# FPGA_7A35T_POWER.net
KiCad netlist of a schematic drawn in Altium Designer
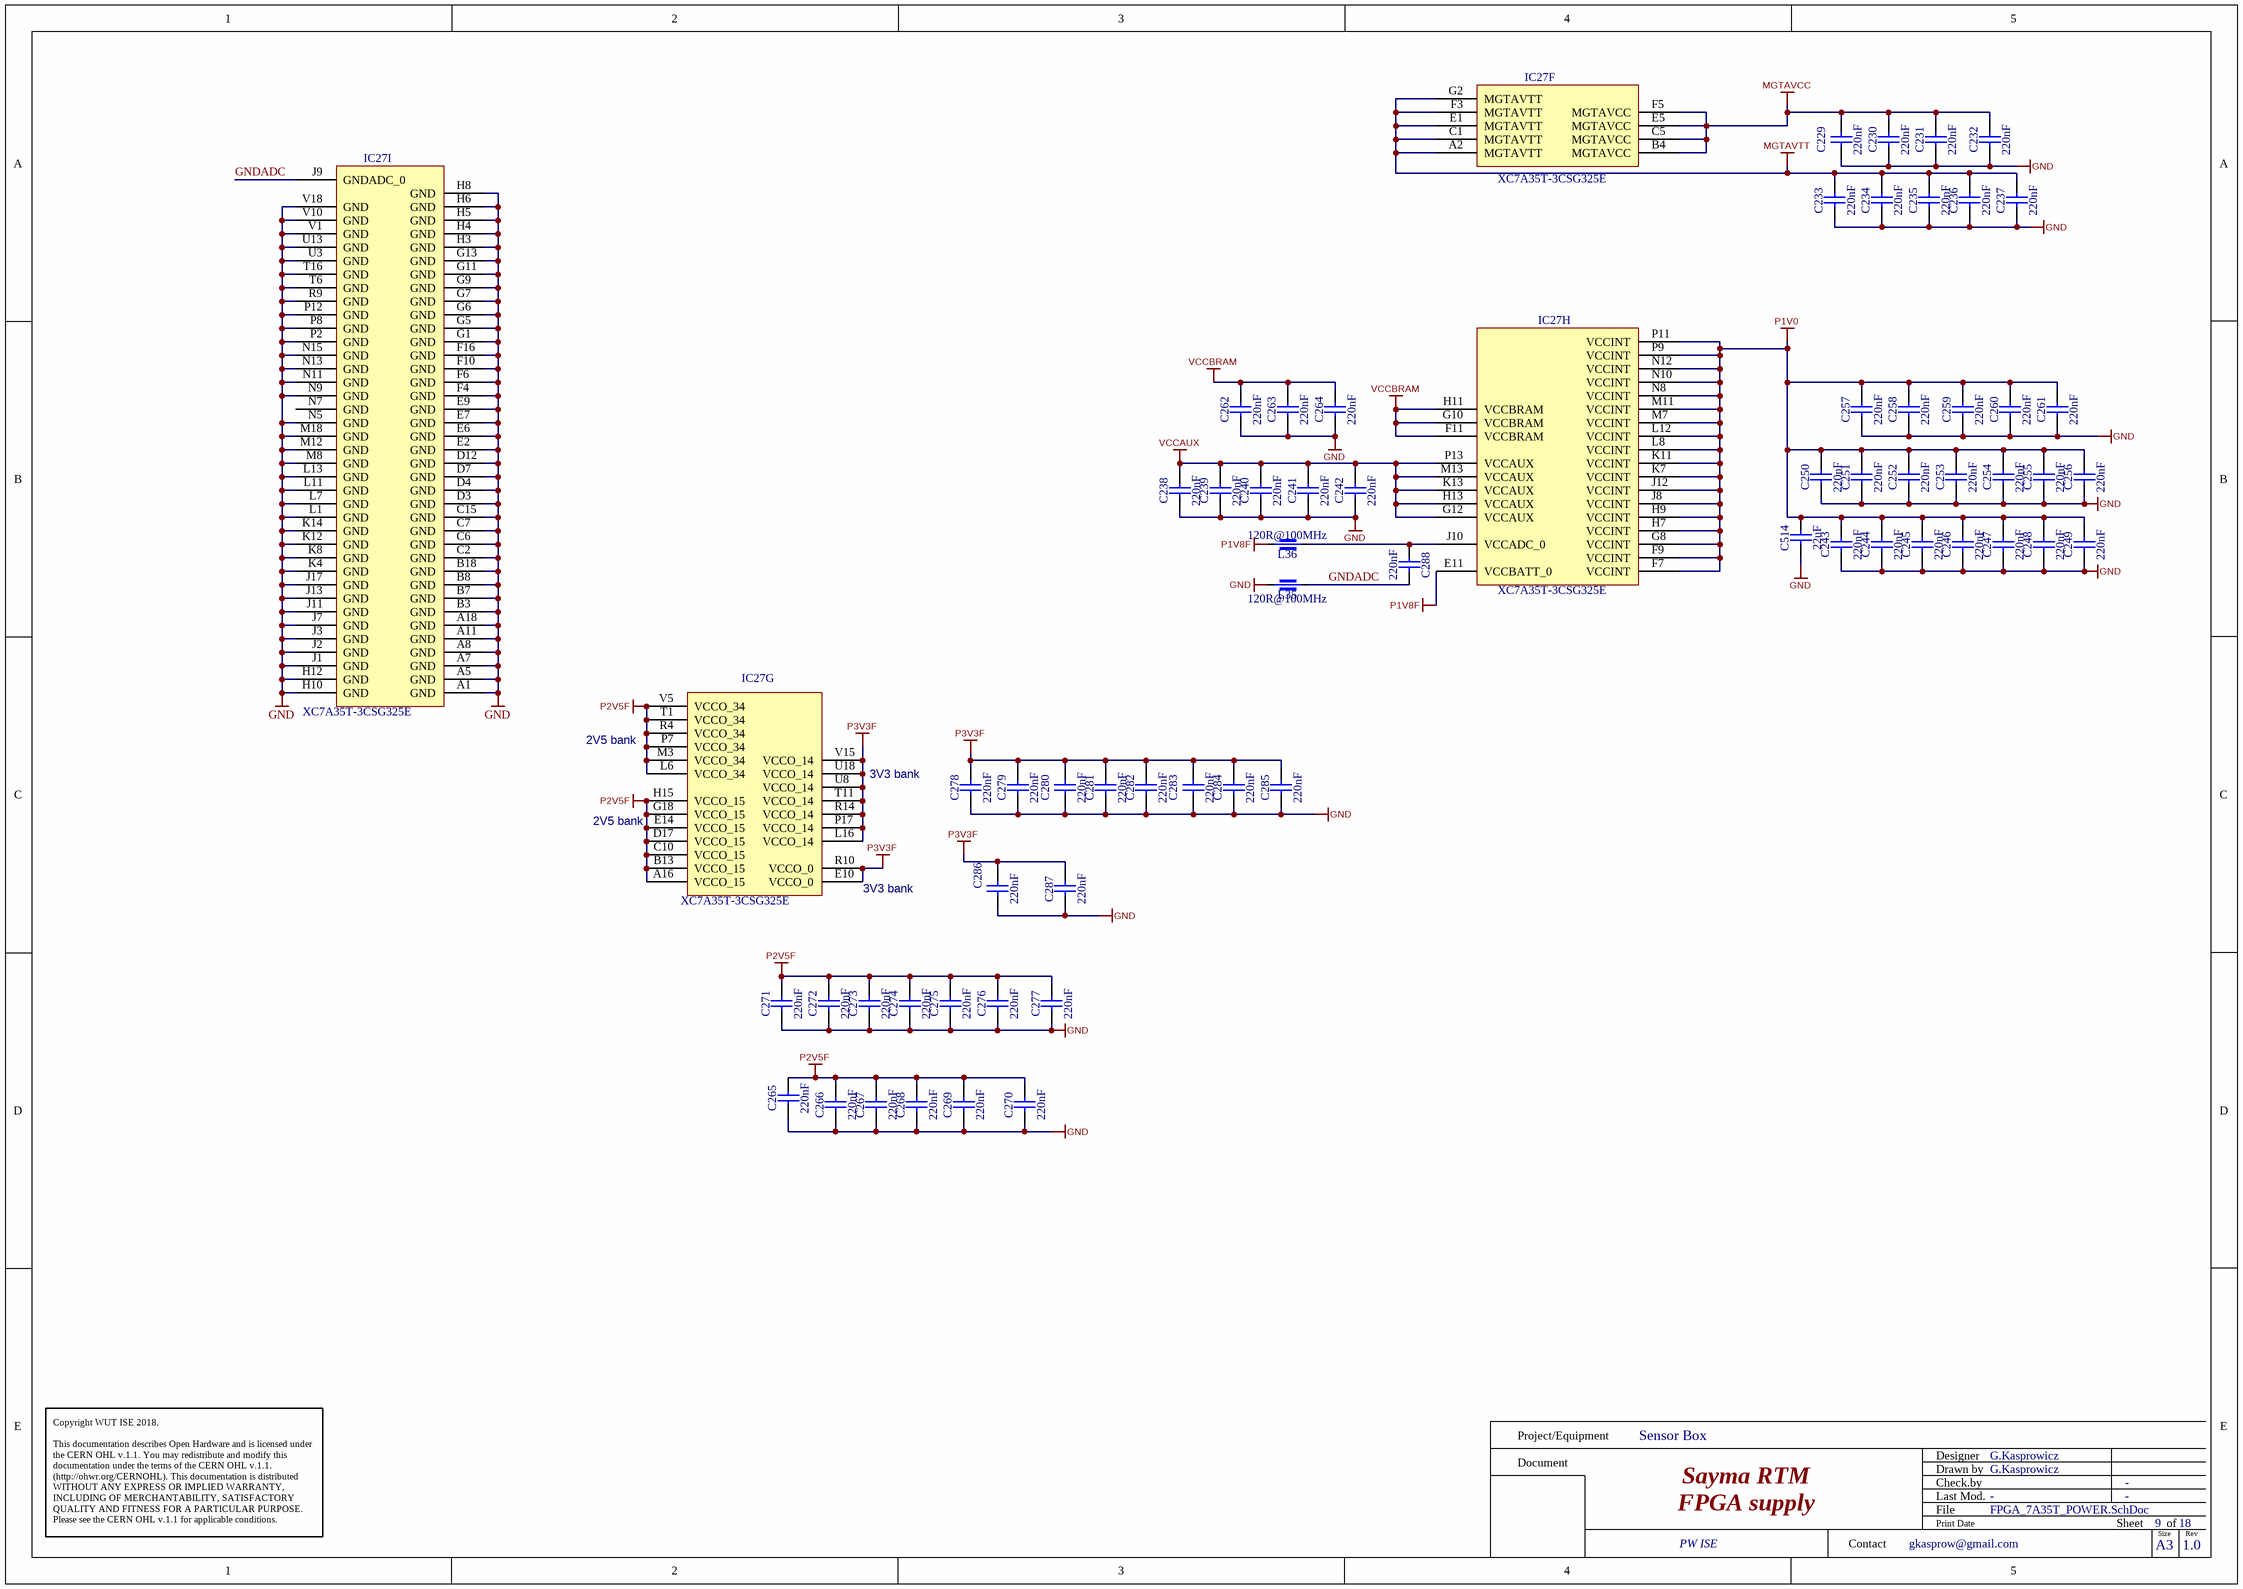
[diagram p0: FPGA_7A35T_POWER.SchDoc]

(export (version "E")
  (design (tool "Eeschema 10.0.6"))
  (components
    (comp (ref "C229")
      (value "220nF")
      (footprint "CAPC0603X33N")
      (description "Non-polarised capacitor")
      (fields
        (field (name "MANUFACTURER PART NUMBER") "CC0201_220NF_6.3V_20%_X5R")
        (field (name "MANUFACTURER") "GENERIC")
        (field (name "AUTHOR") "CERN DEM JLC")
      )
      (libsource (lib "Capacitors") (part "Capacitor - non polarized"))
    )
    (comp (ref "C230")
      (value "220nF")
      (footprint "CAPC0603X33N")
      (description "Non-polarised capacitor")
      (fields
        (field (name "MANUFACTURER PART NUMBER") "CC0201_220NF_6.3V_20%_X5R")
        (field (name "MANUFACTURER") "GENERIC")
        (field (name "AUTHOR") "CERN DEM JLC")
      )
      (libsource (lib "Capacitors") (part "Capacitor - non polarized"))
    )
    (comp (ref "C231")
      (value "220nF")
      (footprint "CAPC0603X33N")
      (description "Non-polarised capacitor")
      (fields
        (field (name "MANUFACTURER PART NUMBER") "CC0201_220NF_6.3V_20%_X5R")
        (field (name "MANUFACTURER") "GENERIC")
        (field (name "AUTHOR") "CERN DEM JLC")
      )
      (libsource (lib "Capacitors") (part "Capacitor - non polarized"))
    )
    (comp (ref "C232")
      (value "220nF")
      (footprint "CAPC0603X33N")
      (description "Non-polarised capacitor")
      (fields
        (field (name "MANUFACTURER PART NUMBER") "CC0201_220NF_6.3V_20%_X5R")
        (field (name "MANUFACTURER") "GENERIC")
        (field (name "AUTHOR") "CERN DEM JLC")
      )
      (libsource (lib "Capacitors") (part "Capacitor - non polarized"))
    )
    (comp (ref "C233")
      (value "220nF")
      (footprint "CAPC0603X33N")
      (description "Non-polarised capacitor")
      (fields
        (field (name "MANUFACTURER PART NUMBER") "CC0201_220NF_6.3V_20%_X5R")
        (field (name "MANUFACTURER") "GENERIC")
        (field (name "AUTHOR") "CERN DEM JLC")
      )
      (libsource (lib "Capacitors") (part "Capacitor - non polarized"))
    )
    (comp (ref "C234")
      (value "220nF")
      (footprint "CAPC0603X33N")
      (description "Non-polarised capacitor")
      (fields
        (field (name "MANUFACTURER PART NUMBER") "CC0201_220NF_6.3V_20%_X5R")
        (field (name "MANUFACTURER") "GENERIC")
        (field (name "AUTHOR") "CERN DEM JLC")
      )
      (libsource (lib "Capacitors") (part "Capacitor - non polarized"))
    )
    (comp (ref "C235")
      (value "220nF")
      (footprint "CAPC0603X33N")
      (description "Non-polarised capacitor")
      (fields
        (field (name "MANUFACTURER PART NUMBER") "CC0201_220NF_6.3V_20%_X5R")
        (field (name "MANUFACTURER") "GENERIC")
        (field (name "AUTHOR") "CERN DEM JLC")
      )
      (libsource (lib "Capacitors") (part "Capacitor - non polarized"))
    )
    (comp (ref "C236")
      (value "220nF")
      (footprint "CAPC0603X33N")
      (description "Non-polarised capacitor")
      (fields
        (field (name "MANUFACTURER PART NUMBER") "CC0201_220NF_6.3V_20%_X5R")
        (field (name "MANUFACTURER") "GENERIC")
        (field (name "AUTHOR") "CERN DEM JLC")
      )
      (libsource (lib "Capacitors") (part "Capacitor - non polarized"))
    )
    (comp (ref "C237")
      (value "220nF")
      (footprint "CAPC0603X33N")
      (description "Non-polarised capacitor")
      (fields
        (field (name "MANUFACTURER PART NUMBER") "CC0201_220NF_6.3V_20%_X5R")
        (field (name "MANUFACTURER") "GENERIC")
        (field (name "AUTHOR") "CERN DEM JLC")
      )
      (libsource (lib "Capacitors") (part "Capacitor - non polarized"))
    )
    (comp (ref "C238")
      (value "220nF")
      (footprint "CAPC0603X33N")
      (description "Non-polarised capacitor")
      (fields
        (field (name "MANUFACTURER PART NUMBER") "CC0201_220NF_6.3V_20%_X5R")
        (field (name "MANUFACTURER") "GENERIC")
        (field (name "AUTHOR") "CERN DEM JLC")
      )
      (libsource (lib "Capacitors") (part "Capacitor - non polarized"))
    )
    (comp (ref "C239")
      (value "220nF")
      (footprint "CAPC0603X33N")
      (description "Non-polarised capacitor")
      (fields
        (field (name "MANUFACTURER PART NUMBER") "CC0201_220NF_6.3V_20%_X5R")
        (field (name "MANUFACTURER") "GENERIC")
        (field (name "AUTHOR") "CERN DEM JLC")
      )
      (libsource (lib "Capacitors") (part "Capacitor - non polarized"))
    )
    (comp (ref "C240")
      (value "220nF")
      (footprint "CAPC0603X33N")
      (description "Non-polarised capacitor")
      (fields
        (field (name "MANUFACTURER PART NUMBER") "CC0201_220NF_6.3V_20%_X5R")
        (field (name "MANUFACTURER") "GENERIC")
        (field (name "AUTHOR") "CERN DEM JLC")
      )
      (libsource (lib "Capacitors") (part "Capacitor - non polarized"))
    )
    (comp (ref "C241")
      (value "220nF")
      (footprint "CAPC0603X33N")
      (description "Non-polarised capacitor")
      (fields
        (field (name "MANUFACTURER PART NUMBER") "CC0201_220NF_6.3V_20%_X5R")
        (field (name "MANUFACTURER") "GENERIC")
        (field (name "AUTHOR") "CERN DEM JLC")
      )
      (libsource (lib "Capacitors") (part "Capacitor - non polarized"))
    )
    (comp (ref "C242")
      (value "220nF")
      (footprint "CAPC0603X33N")
      (description "Non-polarised capacitor")
      (fields
        (field (name "MANUFACTURER PART NUMBER") "CC0201_220NF_6.3V_20%_X5R")
        (field (name "MANUFACTURER") "GENERIC")
        (field (name "AUTHOR") "CERN DEM JLC")
      )
      (libsource (lib "Capacitors") (part "Capacitor - non polarized"))
    )
    (comp (ref "C243")
      (value "220nF")
      (footprint "CAPC0603X33N")
      (description "Non-polarised capacitor")
      (fields
        (field (name "MANUFACTURER PART NUMBER") "CC0201_220NF_6.3V_20%_X5R")
        (field (name "MANUFACTURER") "GENERIC")
        (field (name "AUTHOR") "CERN DEM JLC")
      )
      (libsource (lib "Capacitors") (part "Capacitor - non polarized"))
    )
    (comp (ref "C244")
      (value "220nF")
      (footprint "CAPC0603X33N")
      (description "Non-polarised capacitor")
      (fields
        (field (name "MANUFACTURER PART NUMBER") "CC0201_220NF_6.3V_20%_X5R")
        (field (name "MANUFACTURER") "GENERIC")
        (field (name "AUTHOR") "CERN DEM JLC")
      )
      (libsource (lib "Capacitors") (part "Capacitor - non polarized"))
    )
    (comp (ref "C245")
      (value "220nF")
      (footprint "CAPC0603X33N")
      (description "Non-polarised capacitor")
      (fields
        (field (name "MANUFACTURER PART NUMBER") "CC0201_220NF_6.3V_20%_X5R")
        (field (name "MANUFACTURER") "GENERIC")
        (field (name "AUTHOR") "CERN DEM JLC")
      )
      (libsource (lib "Capacitors") (part "Capacitor - non polarized"))
    )
    (comp (ref "C246")
      (value "220nF")
      (footprint "CAPC0603X33N")
      (description "Non-polarised capacitor")
      (fields
        (field (name "MANUFACTURER PART NUMBER") "CC0201_220NF_6.3V_20%_X5R")
        (field (name "MANUFACTURER") "GENERIC")
        (field (name "AUTHOR") "CERN DEM JLC")
      )
      (libsource (lib "Capacitors") (part "Capacitor - non polarized"))
    )
    (comp (ref "C247")
      (value "220nF")
      (footprint "CAPC0603X33N")
      (description "Non-polarised capacitor")
      (fields
        (field (name "MANUFACTURER PART NUMBER") "CC0201_220NF_6.3V_20%_X5R")
        (field (name "MANUFACTURER") "GENERIC")
        (field (name "AUTHOR") "CERN DEM JLC")
      )
      (libsource (lib "Capacitors") (part "Capacitor - non polarized"))
    )
    (comp (ref "C248")
      (value "220nF")
      (footprint "CAPC0603X33N")
      (description "Non-polarised capacitor")
      (fields
        (field (name "MANUFACTURER PART NUMBER") "CC0201_220NF_6.3V_20%_X5R")
        (field (name "MANUFACTURER") "GENERIC")
        (field (name "AUTHOR") "CERN DEM JLC")
      )
      (libsource (lib "Capacitors") (part "Capacitor - non polarized"))
    )
    (comp (ref "C249")
      (value "220nF")
      (footprint "CAPC0603X33N")
      (description "Non-polarised capacitor")
      (fields
        (field (name "MANUFACTURER PART NUMBER") "CC0201_220NF_6.3V_20%_X5R")
        (field (name "MANUFACTURER") "GENERIC")
        (field (name "AUTHOR") "CERN DEM JLC")
      )
      (libsource (lib "Capacitors") (part "Capacitor - non polarized"))
    )
    (comp (ref "C250")
      (value "220nF")
      (footprint "CAPC0603X33N")
      (description "Non-polarised capacitor")
      (fields
        (field (name "MANUFACTURER PART NUMBER") "CC0201_220NF_6.3V_20%_X5R")
        (field (name "MANUFACTURER") "GENERIC")
        (field (name "AUTHOR") "CERN DEM JLC")
      )
      (libsource (lib "Capacitors") (part "Capacitor - non polarized"))
    )
    (comp (ref "C251")
      (value "220nF")
      (footprint "CAPC0603X33N")
      (description "Non-polarised capacitor")
      (fields
        (field (name "MANUFACTURER PART NUMBER") "CC0201_220NF_6.3V_20%_X5R")
        (field (name "MANUFACTURER") "GENERIC")
        (field (name "AUTHOR") "CERN DEM JLC")
      )
      (libsource (lib "Capacitors") (part "Capacitor - non polarized"))
    )
    (comp (ref "C252")
      (value "220nF")
      (footprint "CAPC0603X33N")
      (description "Non-polarised capacitor")
      (fields
        (field (name "MANUFACTURER PART NUMBER") "CC0201_220NF_6.3V_20%_X5R")
        (field (name "MANUFACTURER") "GENERIC")
        (field (name "AUTHOR") "CERN DEM JLC")
      )
      (libsource (lib "Capacitors") (part "Capacitor - non polarized"))
    )
    (comp (ref "C253")
      (value "220nF")
      (footprint "CAPC0603X33N")
      (description "Non-polarised capacitor")
      (fields
        (field (name "MANUFACTURER PART NUMBER") "CC0201_220NF_6.3V_20%_X5R")
        (field (name "MANUFACTURER") "GENERIC")
        (field (name "AUTHOR") "CERN DEM JLC")
      )
      (libsource (lib "Capacitors") (part "Capacitor - non polarized"))
    )
    (comp (ref "C254")
      (value "220nF")
      (footprint "CAPC0603X33N")
      (description "Non-polarised capacitor")
      (fields
        (field (name "MANUFACTURER PART NUMBER") "CC0201_220NF_6.3V_20%_X5R")
        (field (name "MANUFACTURER") "GENERIC")
        (field (name "AUTHOR") "CERN DEM JLC")
      )
      (libsource (lib "Capacitors") (part "Capacitor - non polarized"))
    )
    (comp (ref "C255")
      (value "220nF")
      (footprint "CAPC0603X33N")
      (description "Non-polarised capacitor")
      (fields
        (field (name "MANUFACTURER PART NUMBER") "CC0201_220NF_6.3V_20%_X5R")
        (field (name "MANUFACTURER") "GENERIC")
        (field (name "AUTHOR") "CERN DEM JLC")
      )
      (libsource (lib "Capacitors") (part "Capacitor - non polarized"))
    )
    (comp (ref "C256")
      (value "220nF")
      (footprint "CAPC0603X33N")
      (description "Non-polarised capacitor")
      (fields
        (field (name "MANUFACTURER PART NUMBER") "CC0201_220NF_6.3V_20%_X5R")
        (field (name "MANUFACTURER") "GENERIC")
        (field (name "AUTHOR") "CERN DEM JLC")
      )
      (libsource (lib "Capacitors") (part "Capacitor - non polarized"))
    )
    (comp (ref "C257")
      (value "220nF")
      (footprint "CAPC0603X33N")
      (description "Non-polarised capacitor")
      (fields
        (field (name "MANUFACTURER PART NUMBER") "CC0201_220NF_6.3V_20%_X5R")
        (field (name "MANUFACTURER") "GENERIC")
        (field (name "AUTHOR") "CERN DEM JLC")
      )
      (libsource (lib "Capacitors") (part "Capacitor - non polarized"))
    )
    (comp (ref "C258")
      (value "220nF")
      (footprint "CAPC0603X33N")
      (description "Non-polarised capacitor")
      (fields
        (field (name "MANUFACTURER PART NUMBER") "CC0201_220NF_6.3V_20%_X5R")
        (field (name "MANUFACTURER") "GENERIC")
        (field (name "AUTHOR") "CERN DEM JLC")
      )
      (libsource (lib "Capacitors") (part "Capacitor - non polarized"))
    )
    (comp (ref "C259")
      (value "220nF")
      (footprint "CAPC0603X33N")
      (description "Non-polarised capacitor")
      (fields
        (field (name "MANUFACTURER PART NUMBER") "CC0201_220NF_6.3V_20%_X5R")
        (field (name "MANUFACTURER") "GENERIC")
        (field (name "AUTHOR") "CERN DEM JLC")
      )
      (libsource (lib "Capacitors") (part "Capacitor - non polarized"))
    )
    (comp (ref "C260")
      (value "220nF")
      (footprint "CAPC0603X33N")
      (description "Non-polarised capacitor")
      (fields
        (field (name "MANUFACTURER PART NUMBER") "CC0201_220NF_6.3V_20%_X5R")
        (field (name "MANUFACTURER") "GENERIC")
        (field (name "AUTHOR") "CERN DEM JLC")
      )
      (libsource (lib "Capacitors") (part "Capacitor - non polarized"))
    )
    (comp (ref "C261")
      (value "220nF")
      (footprint "CAPC0603X33N")
      (description "Non-polarised capacitor")
      (fields
        (field (name "MANUFACTURER PART NUMBER") "CC0201_220NF_6.3V_20%_X5R")
        (field (name "MANUFACTURER") "GENERIC")
        (field (name "AUTHOR") "CERN DEM JLC")
      )
      (libsource (lib "Capacitors") (part "Capacitor - non polarized"))
    )
    (comp (ref "C262")
      (value "220nF")
      (footprint "CAPC0603X33N")
      (description "Non-polarised capacitor")
      (fields
        (field (name "MANUFACTURER PART NUMBER") "CC0201_220NF_6.3V_20%_X5R")
        (field (name "MANUFACTURER") "GENERIC")
        (field (name "AUTHOR") "CERN DEM JLC")
      )
      (libsource (lib "Capacitors") (part "Capacitor - non polarized"))
    )
    (comp (ref "C263")
      (value "220nF")
      (footprint "CAPC0603X33N")
      (description "Non-polarised capacitor")
      (fields
        (field (name "MANUFACTURER PART NUMBER") "CC0201_220NF_6.3V_20%_X5R")
        (field (name "MANUFACTURER") "GENERIC")
        (field (name "AUTHOR") "CERN DEM JLC")
      )
      (libsource (lib "Capacitors") (part "Capacitor - non polarized"))
    )
    (comp (ref "C264")
      (value "220nF")
      (footprint "CAPC0603X33N")
      (description "Non-polarised capacitor")
      (fields
        (field (name "MANUFACTURER PART NUMBER") "CC0201_220NF_6.3V_20%_X5R")
        (field (name "MANUFACTURER") "GENERIC")
        (field (name "AUTHOR") "CERN DEM JLC")
      )
      (libsource (lib "Capacitors") (part "Capacitor - non polarized"))
    )
    (comp (ref "C265")
      (value "220nF")
      (footprint "CAPC0603X33N")
      (description "Non-polarised capacitor")
      (fields
        (field (name "MANUFACTURER PART NUMBER") "CC0201_220NF_6.3V_20%_X5R")
        (field (name "MANUFACTURER") "GENERIC")
        (field (name "AUTHOR") "CERN DEM JLC")
      )
      (libsource (lib "Capacitors") (part "Capacitor - non polarized"))
    )
    (comp (ref "C266")
      (value "220nF")
      (footprint "CAPC0603X33N")
      (description "Non-polarised capacitor")
      (fields
        (field (name "MANUFACTURER PART NUMBER") "CC0201_220NF_6.3V_20%_X5R")
        (field (name "MANUFACTURER") "GENERIC")
        (field (name "AUTHOR") "CERN DEM JLC")
      )
      (libsource (lib "Capacitors") (part "Capacitor - non polarized"))
    )
    (comp (ref "C267")
      (value "220nF")
      (footprint "CAPC0603X33N")
      (description "Non-polarised capacitor")
      (fields
        (field (name "MANUFACTURER PART NUMBER") "CC0201_220NF_6.3V_20%_X5R")
        (field (name "MANUFACTURER") "GENERIC")
        (field (name "AUTHOR") "CERN DEM JLC")
      )
      (libsource (lib "Capacitors") (part "Capacitor - non polarized"))
    )
    (comp (ref "C268")
      (value "220nF")
      (footprint "CAPC0603X33N")
      (description "Non-polarised capacitor")
      (fields
        (field (name "MANUFACTURER PART NUMBER") "CC0201_220NF_6.3V_20%_X5R")
        (field (name "MANUFACTURER") "GENERIC")
        (field (name "AUTHOR") "CERN DEM JLC")
      )
      (libsource (lib "Capacitors") (part "Capacitor - non polarized"))
    )
    (comp (ref "C269")
      (value "220nF")
      (footprint "CAPC0603X33N")
      (description "Non-polarised capacitor")
      (fields
        (field (name "MANUFACTURER PART NUMBER") "CC0201_220NF_6.3V_20%_X5R")
        (field (name "MANUFACTURER") "GENERIC")
        (field (name "AUTHOR") "CERN DEM JLC")
      )
      (libsource (lib "Capacitors") (part "Capacitor - non polarized"))
    )
    (comp (ref "C270")
      (value "220nF")
      (footprint "CAPC0603X33N")
      (description "Non-polarised capacitor")
      (fields
        (field (name "MANUFACTURER PART NUMBER") "CC0201_220NF_6.3V_20%_X5R")
        (field (name "MANUFACTURER") "GENERIC")
        (field (name "AUTHOR") "CERN DEM JLC")
      )
      (libsource (lib "Capacitors") (part "Capacitor - non polarized"))
    )
    (comp (ref "C271")
      (value "220nF")
      (footprint "CAPC0603X33N")
      (description "Non-polarised capacitor")
      (fields
        (field (name "MANUFACTURER PART NUMBER") "CC0201_220NF_6.3V_20%_X5R")
        (field (name "MANUFACTURER") "GENERIC")
        (field (name "AUTHOR") "CERN DEM JLC")
      )
      (libsource (lib "Capacitors") (part "Capacitor - non polarized"))
    )
    (comp (ref "C272")
      (value "220nF")
      (footprint "CAPC0603X33N")
      (description "Non-polarised capacitor")
      (fields
        (field (name "MANUFACTURER PART NUMBER") "CC0201_220NF_6.3V_20%_X5R")
        (field (name "MANUFACTURER") "GENERIC")
        (field (name "AUTHOR") "CERN DEM JLC")
      )
      (libsource (lib "Capacitors") (part "Capacitor - non polarized"))
    )
    (comp (ref "C273")
      (value "220nF")
      (footprint "CAPC0603X33N")
      (description "Non-polarised capacitor")
      (fields
        (field (name "MANUFACTURER PART NUMBER") "CC0201_220NF_6.3V_20%_X5R")
        (field (name "MANUFACTURER") "GENERIC")
        (field (name "AUTHOR") "CERN DEM JLC")
      )
      (libsource (lib "Capacitors") (part "Capacitor - non polarized"))
    )
    (comp (ref "C274")
      (value "220nF")
      (footprint "CAPC0603X33N")
      (description "Non-polarised capacitor")
      (fields
        (field (name "MANUFACTURER PART NUMBER") "CC0201_220NF_6.3V_20%_X5R")
        (field (name "MANUFACTURER") "GENERIC")
        (field (name "AUTHOR") "CERN DEM JLC")
      )
      (libsource (lib "Capacitors") (part "Capacitor - non polarized"))
    )
    (comp (ref "C275")
      (value "220nF")
      (footprint "CAPC0603X33N")
      (description "Non-polarised capacitor")
      (fields
        (field (name "MANUFACTURER PART NUMBER") "CC0201_220NF_6.3V_20%_X5R")
        (field (name "MANUFACTURER") "GENERIC")
        (field (name "AUTHOR") "CERN DEM JLC")
      )
      (libsource (lib "Capacitors") (part "Capacitor - non polarized"))
    )
    (comp (ref "C276")
      (value "220nF")
      (footprint "CAPC0603X33N")
      (description "Non-polarised capacitor")
      (fields
        (field (name "MANUFACTURER PART NUMBER") "CC0201_220NF_6.3V_20%_X5R")
        (field (name "MANUFACTURER") "GENERIC")
        (field (name "AUTHOR") "CERN DEM JLC")
      )
      (libsource (lib "Capacitors") (part "Capacitor - non polarized"))
    )
    (comp (ref "C277")
      (value "220nF")
      (footprint "CAPC0603X33N")
      (description "Non-polarised capacitor")
      (fields
        (field (name "MANUFACTURER PART NUMBER") "CC0201_220NF_6.3V_20%_X5R")
        (field (name "MANUFACTURER") "GENERIC")
        (field (name "AUTHOR") "CERN DEM JLC")
      )
      (libsource (lib "Capacitors") (part "Capacitor - non polarized"))
    )
    (comp (ref "C278")
      (value "220nF")
      (footprint "CAPC0603X33N")
      (description "Non-polarised capacitor")
      (fields
        (field (name "MANUFACTURER PART NUMBER") "CC0201_220NF_6.3V_20%_X5R")
        (field (name "MANUFACTURER") "GENERIC")
        (field (name "AUTHOR") "CERN DEM JLC")
      )
      (libsource (lib "Capacitors") (part "Capacitor - non polarized"))
    )
    (comp (ref "C279")
      (value "220nF")
      (footprint "CAPC0603X33N")
      (description "Non-polarised capacitor")
      (fields
        (field (name "MANUFACTURER PART NUMBER") "CC0201_220NF_6.3V_20%_X5R")
        (field (name "MANUFACTURER") "GENERIC")
        (field (name "AUTHOR") "CERN DEM JLC")
      )
      (libsource (lib "Capacitors") (part "Capacitor - non polarized"))
    )
    (comp (ref "C280")
      (value "220nF")
      (footprint "CAPC0603X33N")
      (description "Non-polarised capacitor")
      (fields
        (field (name "MANUFACTURER PART NUMBER") "CC0201_220NF_6.3V_20%_X5R")
        (field (name "MANUFACTURER") "GENERIC")
        (field (name "AUTHOR") "CERN DEM JLC")
      )
      (libsource (lib "Capacitors") (part "Capacitor - non polarized"))
    )
    (comp (ref "C281")
      (value "220nF")
      (footprint "CAPC0603X33N")
      (description "Non-polarised capacitor")
      (fields
        (field (name "MANUFACTURER PART NUMBER") "CC0201_220NF_6.3V_20%_X5R")
        (field (name "MANUFACTURER") "GENERIC")
        (field (name "AUTHOR") "CERN DEM JLC")
      )
      (libsource (lib "Capacitors") (part "Capacitor - non polarized"))
    )
    (comp (ref "C282")
      (value "220nF")
      (footprint "CAPC0603X33N")
      (description "Non-polarised capacitor")
      (fields
        (field (name "MANUFACTURER PART NUMBER") "CC0201_220NF_6.3V_20%_X5R")
        (field (name "MANUFACTURER") "GENERIC")
        (field (name "AUTHOR") "CERN DEM JLC")
      )
      (libsource (lib "Capacitors") (part "Capacitor - non polarized"))
    )
    (comp (ref "C283")
      (value "220nF")
      (footprint "CAPC0603X33N")
      (description "Non-polarised capacitor")
      (fields
        (field (name "MANUFACTURER PART NUMBER") "CC0201_220NF_6.3V_20%_X5R")
        (field (name "MANUFACTURER") "GENERIC")
        (field (name "AUTHOR") "CERN DEM JLC")
      )
      (libsource (lib "Capacitors") (part "Capacitor - non polarized"))
    )
    (comp (ref "C284")
      (value "220nF")
      (footprint "CAPC0603X33N")
      (description "Non-polarised capacitor")
      (fields
        (field (name "MANUFACTURER PART NUMBER") "CC0201_220NF_6.3V_20%_X5R")
        (field (name "MANUFACTURER") "GENERIC")
        (field (name "AUTHOR") "CERN DEM JLC")
      )
      (libsource (lib "Capacitors") (part "Capacitor - non polarized"))
    )
    (comp (ref "C285")
      (value "220nF")
      (footprint "CAPC0603X33N")
      (description "Non-polarised capacitor")
      (fields
        (field (name "MANUFACTURER PART NUMBER") "CC0201_220NF_6.3V_20%_X5R")
        (field (name "MANUFACTURER") "GENERIC")
        (field (name "AUTHOR") "CERN DEM JLC")
      )
      (libsource (lib "Capacitors") (part "Capacitor - non polarized"))
    )
    (comp (ref "C286")
      (value "220nF")
      (footprint "CAPC0603X33N")
      (description "Non-polarised capacitor")
      (fields
        (field (name "MANUFACTURER PART NUMBER") "CC0201_220NF_6.3V_20%_X5R")
        (field (name "MANUFACTURER") "GENERIC")
        (field (name "AUTHOR") "CERN DEM JLC")
      )
      (libsource (lib "Capacitors") (part "Capacitor - non polarized"))
    )
    (comp (ref "C287")
      (value "220nF")
      (footprint "CAPC0603X33N")
      (description "Non-polarised capacitor")
      (fields
        (field (name "MANUFACTURER PART NUMBER") "CC0201_220NF_6.3V_20%_X5R")
        (field (name "MANUFACTURER") "GENERIC")
        (field (name "AUTHOR") "CERN DEM JLC")
      )
      (libsource (lib "Capacitors") (part "Capacitor - non polarized"))
    )
    (comp (ref "C288")
      (value "220nF")
      (footprint "CAPC0603X33N")
      (description "Non-polarised capacitor")
      (fields
        (field (name "MANUFACTURER PART NUMBER") "CC0201_220NF_6.3V_20%_X5R")
        (field (name "MANUFACTURER") "GENERIC")
        (field (name "AUTHOR") "CERN DEM JLC")
      )
      (libsource (lib "Capacitors") (part "Capacitor - non polarized"))
    )
    (comp (ref "C514")
      (value "22uF")
      (footprint "CAPC2012X135N")
      (description "Non-polarised capacitor")
      (fields
        (field (name "MANUFACTURER PART NUMBER") "CC0805_22UF_6.3V_20%_X5R")
        (field (name "MANUFACTURER") "GENERIC")
        (field (name "AUTHOR") "CERN DEM JLC")
      )
      (libsource (lib "Capacitors") (part "Capacitor - non polarized"))
    )
    (comp (ref "IC27")
      (value "XC7A35T-3CSG325E")
      (footprint "CSG325")
      (description "Artix-7 FPGA, 150 User I/Os, 4 GTP, 324-Ball BGA, Speed Grade 3, Extended Grade, Pb-Free")
      (fields (field (name "MANUFACTURER") "Xilinx"))
      (libsource (lib "Altium Content Vault") (part "XLNX-XC7A35T-CSG325"))
    )
    (comp (ref "L35")
      (value "120R@100MHz")
      (footprint "INDC1005X55N")
      (fields
        (field (name "MANUFACTURER PART NUMBER") "BLM15PX121SN1D")
        (field (name "MANUFACTURER") "MURATA")
        (field (name "PART NUMBER") "IND0402_MURATA_BLM15PX121SN1D")
        (field (name "AUTHOR") "CERN DEM JMW")
      )
      (libsource (lib "Inductors & Transformers") (part "Ferrite Bead"))
    )
    (comp (ref "L36")
      (value "120R@100MHz")
      (footprint "INDC1005X55N")
      (fields
        (field (name "MANUFACTURER PART NUMBER") "BLM15PX121SN1D")
        (field (name "MANUFACTURER") "MURATA")
        (field (name "PART NUMBER") "IND0402_MURATA_BLM15PX121SN1D")
        (field (name "AUTHOR") "CERN DEM JMW")
      )
      (libsource (lib "Inductors & Transformers") (part "Ferrite Bead"))
    )
  )
  (nets
    (net (code "1") (name "/GNDADC") (class "Default")
      (node (ref "C288") (pin "2") (pinfunction "2_2") (pintype "passive"))
      (node (ref "IC27") (pin "J9") (pinfunction "GNDADC_0_J9") (pintype "power_in"))
      (node (ref "L35") (pin "2") (pinfunction "2_2") (pintype "passive"))
    )
    (net (code "2") (name "GND") (class "Default")
      (node (ref "C229") (pin "1") (pinfunction "1_1") (pintype "passive"))
      (node (ref "C230") (pin "1") (pinfunction "1_1") (pintype "passive"))
      (node (ref "C231") (pin "1") (pinfunction "1_1") (pintype "passive"))
      (node (ref "C232") (pin "1") (pinfunction "1_1") (pintype "passive"))
      (node (ref "C233") (pin "1") (pinfunction "1_1") (pintype "passive"))
      (node (ref "C234") (pin "1") (pinfunction "1_1") (pintype "passive"))
      (node (ref "C235") (pin "1") (pinfunction "1_1") (pintype "passive"))
      (node (ref "C236") (pin "1") (pinfunction "1_1") (pintype "passive"))
      (node (ref "C237") (pin "1") (pinfunction "1_1") (pintype "passive"))
      (node (ref "C238") (pin "1") (pinfunction "1_1") (pintype "passive"))
      (node (ref "C239") (pin "1") (pinfunction "1_1") (pintype "passive"))
      (node (ref "C240") (pin "1") (pinfunction "1_1") (pintype "passive"))
      (node (ref "C241") (pin "1") (pinfunction "1_1") (pintype "passive"))
      (node (ref "C242") (pin "1") (pinfunction "1_1") (pintype "passive"))
      (node (ref "C243") (pin "1") (pinfunction "1_1") (pintype "passive"))
      (node (ref "C244") (pin "1") (pinfunction "1_1") (pintype "passive"))
      (node (ref "C245") (pin "1") (pinfunction "1_1") (pintype "passive"))
      (node (ref "C246") (pin "1") (pinfunction "1_1") (pintype "passive"))
      (node (ref "C247") (pin "1") (pinfunction "1_1") (pintype "passive"))
      (node (ref "C248") (pin "1") (pinfunction "1_1") (pintype "passive"))
      (node (ref "C249") (pin "1") (pinfunction "1_1") (pintype "passive"))
      (node (ref "C250") (pin "1") (pinfunction "1_1") (pintype "passive"))
      (node (ref "C251") (pin "1") (pinfunction "1_1") (pintype "passive"))
      (node (ref "C252") (pin "1") (pinfunction "1_1") (pintype "passive"))
      (node (ref "C253") (pin "1") (pinfunction "1_1") (pintype "passive"))
      (node (ref "C254") (pin "1") (pinfunction "1_1") (pintype "passive"))
      (node (ref "C255") (pin "1") (pinfunction "1_1") (pintype "passive"))
      (node (ref "C256") (pin "1") (pinfunction "1_1") (pintype "passive"))
      (node (ref "C257") (pin "1") (pinfunction "1_1") (pintype "passive"))
      (node (ref "C258") (pin "1") (pinfunction "1_1") (pintype "passive"))
      (node (ref "C259") (pin "1") (pinfunction "1_1") (pintype "passive"))
      (node (ref "C260") (pin "1") (pinfunction "1_1") (pintype "passive"))
      (node (ref "C261") (pin "1") (pinfunction "1_1") (pintype "passive"))
      (node (ref "C262") (pin "1") (pinfunction "1_1") (pintype "passive"))
      (node (ref "C263") (pin "1") (pinfunction "1_1") (pintype "passive"))
      (node (ref "C264") (pin "1") (pinfunction "1_1") (pintype "passive"))
      (node (ref "C265") (pin "1") (pinfunction "1_1") (pintype "passive"))
      (node (ref "C266") (pin "1") (pinfunction "1_1") (pintype "passive"))
      (node (ref "C267") (pin "1") (pinfunction "1_1") (pintype "passive"))
      (node (ref "C268") (pin "1") (pinfunction "1_1") (pintype "passive"))
      (node (ref "C269") (pin "1") (pinfunction "1_1") (pintype "passive"))
      (node (ref "C270") (pin "1") (pinfunction "1_1") (pintype "passive"))
      (node (ref "C271") (pin "1") (pinfunction "1_1") (pintype "passive"))
      (node (ref "C272") (pin "1") (pinfunction "1_1") (pintype "passive"))
      (node (ref "C273") (pin "1") (pinfunction "1_1") (pintype "passive"))
      (node (ref "C274") (pin "1") (pinfunction "1_1") (pintype "passive"))
      (node (ref "C275") (pin "1") (pinfunction "1_1") (pintype "passive"))
      (node (ref "C276") (pin "1") (pinfunction "1_1") (pintype "passive"))
      (node (ref "C277") (pin "1") (pinfunction "1_1") (pintype "passive"))
      (node (ref "C278") (pin "1") (pinfunction "1_1") (pintype "passive"))
      (node (ref "C279") (pin "1") (pinfunction "1_1") (pintype "passive"))
      (node (ref "C280") (pin "1") (pinfunction "1_1") (pintype "passive"))
      (node (ref "C281") (pin "1") (pinfunction "1_1") (pintype "passive"))
      (node (ref "C282") (pin "1") (pinfunction "1_1") (pintype "passive"))
      (node (ref "C283") (pin "1") (pinfunction "1_1") (pintype "passive"))
      (node (ref "C284") (pin "1") (pinfunction "1_1") (pintype "passive"))
      (node (ref "C285") (pin "1") (pinfunction "1_1") (pintype "passive"))
      (node (ref "C286") (pin "1") (pinfunction "1_1") (pintype "passive"))
      (node (ref "C287") (pin "1") (pinfunction "1_1") (pintype "passive"))
      (node (ref "C514") (pin "1") (pinfunction "1_1") (pintype "passive"))
      (node (ref "IC27") (pin "A1") (pinfunction "GND_A1") (pintype "power_in"))
      (node (ref "IC27") (pin "A11") (pinfunction "GND_A11") (pintype "power_in"))
      (node (ref "IC27") (pin "A18") (pinfunction "GND_A18") (pintype "power_in"))
      (node (ref "IC27") (pin "A5") (pinfunction "GND_A5") (pintype "power_in"))
      (node (ref "IC27") (pin "A7") (pinfunction "GND_A7") (pintype "power_in"))
      (node (ref "IC27") (pin "A8") (pinfunction "GND_A8") (pintype "power_in"))
      (node (ref "IC27") (pin "B18") (pinfunction "GND_B18") (pintype "power_in"))
      (node (ref "IC27") (pin "B3") (pinfunction "GND_B3") (pintype "power_in"))
      (node (ref "IC27") (pin "B7") (pinfunction "GND_B7") (pintype "power_in"))
      (node (ref "IC27") (pin "B8") (pinfunction "GND_B8") (pintype "power_in"))
      (node (ref "IC27") (pin "C15") (pinfunction "GND_C15") (pintype "power_in"))
      (node (ref "IC27") (pin "C2") (pinfunction "GND_C2") (pintype "power_in"))
      (node (ref "IC27") (pin "C6") (pinfunction "GND_C6") (pintype "power_in"))
      (node (ref "IC27") (pin "C7") (pinfunction "GND_C7") (pintype "power_in"))
      (node (ref "IC27") (pin "D12") (pinfunction "GND_D12") (pintype "power_in"))
      (node (ref "IC27") (pin "D3") (pinfunction "GND_D3") (pintype "power_in"))
      (node (ref "IC27") (pin "D4") (pinfunction "GND_D4") (pintype "power_in"))
      (node (ref "IC27") (pin "D7") (pinfunction "GND_D7") (pintype "power_in"))
      (node (ref "IC27") (pin "E2") (pinfunction "GND_E2") (pintype "power_in"))
      (node (ref "IC27") (pin "E6") (pinfunction "GND_E6") (pintype "power_in"))
      (node (ref "IC27") (pin "E7") (pinfunction "GND_E7") (pintype "power_in"))
      (node (ref "IC27") (pin "E9") (pinfunction "GND_E9") (pintype "power_in"))
      (node (ref "IC27") (pin "F10") (pinfunction "GND_F10") (pintype "power_in"))
      (node (ref "IC27") (pin "F16") (pinfunction "GND_F16") (pintype "power_in"))
      (node (ref "IC27") (pin "F4") (pinfunction "GND_F4") (pintype "power_in"))
      (node (ref "IC27") (pin "F6") (pinfunction "GND_F6") (pintype "power_in"))
      (node (ref "IC27") (pin "G1") (pinfunction "GND_G1") (pintype "power_in"))
      (node (ref "IC27") (pin "G11") (pinfunction "GND_G11") (pintype "power_in"))
      (node (ref "IC27") (pin "G13") (pinfunction "GND_G13") (pintype "power_in"))
      (node (ref "IC27") (pin "G5") (pinfunction "GND_G5") (pintype "power_in"))
      (node (ref "IC27") (pin "G6") (pinfunction "GND_G6") (pintype "power_in"))
      (node (ref "IC27") (pin "G7") (pinfunction "GND_G7") (pintype "power_in"))
      (node (ref "IC27") (pin "G9") (pinfunction "GND_G9") (pintype "power_in"))
      (node (ref "IC27") (pin "H10") (pinfunction "GND_H10") (pintype "power_in"))
      (node (ref "IC27") (pin "H12") (pinfunction "GND_H12") (pintype "power_in"))
      (node (ref "IC27") (pin "H3") (pinfunction "GND_H3") (pintype "power_in"))
      (node (ref "IC27") (pin "H4") (pinfunction "GND_H4") (pintype "power_in"))
      (node (ref "IC27") (pin "H5") (pinfunction "GND_H5") (pintype "power_in"))
      (node (ref "IC27") (pin "H6") (pinfunction "GND_H6") (pintype "power_in"))
      (node (ref "IC27") (pin "H8") (pinfunction "GND_H8") (pintype "power_in"))
      (node (ref "IC27") (pin "J1") (pinfunction "GND_J1") (pintype "power_in"))
      (node (ref "IC27") (pin "J11") (pinfunction "GND_J11") (pintype "power_in"))
      (node (ref "IC27") (pin "J13") (pinfunction "GND_J13") (pintype "power_in"))
      (node (ref "IC27") (pin "J17") (pinfunction "GND_J17") (pintype "power_in"))
      (node (ref "IC27") (pin "J2") (pinfunction "GND_J2") (pintype "power_in"))
      (node (ref "IC27") (pin "J3") (pinfunction "GND_J3") (pintype "power_in"))
      (node (ref "IC27") (pin "J7") (pinfunction "GND_J7") (pintype "power_in"))
      (node (ref "IC27") (pin "K12") (pinfunction "GND_K12") (pintype "power_in"))
      (node (ref "IC27") (pin "K14") (pinfunction "GND_K14") (pintype "power_in"))
      (node (ref "IC27") (pin "K4") (pinfunction "GND_K4") (pintype "power_in"))
      (node (ref "IC27") (pin "K8") (pinfunction "GND_K8") (pintype "power_in"))
      (node (ref "IC27") (pin "L1") (pinfunction "GND_L1") (pintype "power_in"))
      (node (ref "IC27") (pin "L11") (pinfunction "GND_L11") (pintype "power_in"))
      (node (ref "IC27") (pin "L13") (pinfunction "GND_L13") (pintype "power_in"))
      (node (ref "IC27") (pin "L7") (pinfunction "GND_L7") (pintype "power_in"))
      (node (ref "IC27") (pin "M12") (pinfunction "GND_M12") (pintype "power_in"))
      (node (ref "IC27") (pin "M18") (pinfunction "GND_M18") (pintype "power_in"))
      (node (ref "IC27") (pin "M8") (pinfunction "GND_M8") (pintype "power_in"))
      (node (ref "IC27") (pin "N11") (pinfunction "GND_N11") (pintype "power_in"))
      (node (ref "IC27") (pin "N13") (pinfunction "GND_N13") (pintype "power_in"))
      (node (ref "IC27") (pin "N15") (pinfunction "GND_N15") (pintype "power_in"))
      (node (ref "IC27") (pin "N5") (pinfunction "GND_N5") (pintype "power_in"))
      (node (ref "IC27") (pin "N9") (pinfunction "GND_N9") (pintype "power_in"))
      (node (ref "IC27") (pin "P12") (pinfunction "GND_P12") (pintype "power_in"))
      (node (ref "IC27") (pin "P2") (pinfunction "GND_P2") (pintype "power_in"))
      (node (ref "IC27") (pin "P8") (pinfunction "GND_P8") (pintype "power_in"))
      (node (ref "IC27") (pin "R9") (pinfunction "GND_R9") (pintype "power_in"))
      (node (ref "IC27") (pin "T16") (pinfunction "GND_T16") (pintype "power_in"))
      (node (ref "IC27") (pin "T6") (pinfunction "GND_T6") (pintype "power_in"))
      (node (ref "IC27") (pin "U13") (pinfunction "GND_U13") (pintype "power_in"))
      (node (ref "IC27") (pin "U3") (pinfunction "GND_U3") (pintype "power_in"))
      (node (ref "IC27") (pin "V1") (pinfunction "GND_V1") (pintype "power_in"))
      (node (ref "IC27") (pin "V10") (pinfunction "GND_V10") (pintype "power_in"))
      (node (ref "IC27") (pin "V18") (pinfunction "GND_V18") (pintype "power_in"))
      (node (ref "L35") (pin "1") (pinfunction "1_1") (pintype "passive"))
    )
    (net (code "3") (name "MGTAVCC") (class "Default")
      (node (ref "C229") (pin "2") (pinfunction "2_2") (pintype "passive"))
      (node (ref "C230") (pin "2") (pinfunction "2_2") (pintype "passive"))
      (node (ref "C231") (pin "2") (pinfunction "2_2") (pintype "passive"))
      (node (ref "C232") (pin "2") (pinfunction "2_2") (pintype "passive"))
      (node (ref "IC27") (pin "B4") (pinfunction "MGTAVCC_B4") (pintype "power_in"))
      (node (ref "IC27") (pin "C5") (pinfunction "MGTAVCC_C5") (pintype "power_in"))
      (node (ref "IC27") (pin "E5") (pinfunction "MGTAVCC_E5") (pintype "power_in"))
      (node (ref "IC27") (pin "F5") (pinfunction "MGTAVCC_F5") (pintype "power_in"))
    )
    (net (code "4") (name "MGTAVTT") (class "Default")
      (node (ref "C233") (pin "2") (pinfunction "2_2") (pintype "passive"))
      (node (ref "C234") (pin "2") (pinfunction "2_2") (pintype "passive"))
      (node (ref "C235") (pin "2") (pinfunction "2_2") (pintype "passive"))
      (node (ref "C236") (pin "2") (pinfunction "2_2") (pintype "passive"))
      (node (ref "C237") (pin "2") (pinfunction "2_2") (pintype "passive"))
      (node (ref "IC27") (pin "A2") (pinfunction "MGTAVTT_A2") (pintype "power_in"))
      (node (ref "IC27") (pin "C1") (pinfunction "MGTAVTT_C1") (pintype "power_in"))
      (node (ref "IC27") (pin "E1") (pinfunction "MGTAVTT_E1") (pintype "power_in"))
      (node (ref "IC27") (pin "F3") (pinfunction "MGTAVTT_F3") (pintype "power_in"))
      (node (ref "IC27") (pin "G2") (pinfunction "MGTAVTT_G2") (pintype "power_in"))
    )
    (net (code "5") (name "Net-(IC27H-VCCADC_0)") (class "Default")
      (node (ref "C288") (pin "1") (pinfunction "1_1") (pintype "passive"))
      (node (ref "IC27") (pin "J10") (pinfunction "VCCADC_0_J10") (pintype "power_in"))
      (node (ref "L36") (pin "2") (pinfunction "2_2") (pintype "passive"))
    )
    (net (code "6") (name "P1V0") (class "Default")
      (node (ref "C243") (pin "2") (pinfunction "2_2") (pintype "passive"))
      (node (ref "C244") (pin "2") (pinfunction "2_2") (pintype "passive"))
      (node (ref "C245") (pin "2") (pinfunction "2_2") (pintype "passive"))
      (node (ref "C246") (pin "2") (pinfunction "2_2") (pintype "passive"))
      (node (ref "C247") (pin "2") (pinfunction "2_2") (pintype "passive"))
      (node (ref "C248") (pin "2") (pinfunction "2_2") (pintype "passive"))
      (node (ref "C249") (pin "2") (pinfunction "2_2") (pintype "passive"))
      (node (ref "C250") (pin "2") (pinfunction "2_2") (pintype "passive"))
      (node (ref "C251") (pin "2") (pinfunction "2_2") (pintype "passive"))
      (node (ref "C252") (pin "2") (pinfunction "2_2") (pintype "passive"))
      (node (ref "C253") (pin "2") (pinfunction "2_2") (pintype "passive"))
      (node (ref "C254") (pin "2") (pinfunction "2_2") (pintype "passive"))
      (node (ref "C255") (pin "2") (pinfunction "2_2") (pintype "passive"))
      (node (ref "C256") (pin "2") (pinfunction "2_2") (pintype "passive"))
      (node (ref "C257") (pin "2") (pinfunction "2_2") (pintype "passive"))
      (node (ref "C258") (pin "2") (pinfunction "2_2") (pintype "passive"))
      (node (ref "C259") (pin "2") (pinfunction "2_2") (pintype "passive"))
      (node (ref "C260") (pin "2") (pinfunction "2_2") (pintype "passive"))
      (node (ref "C261") (pin "2") (pinfunction "2_2") (pintype "passive"))
      (node (ref "C514") (pin "2") (pinfunction "2_2") (pintype "passive"))
      (node (ref "IC27") (pin "F7") (pinfunction "VCCINT_F7") (pintype "power_in"))
      (node (ref "IC27") (pin "F9") (pinfunction "VCCINT_F9") (pintype "power_in"))
      (node (ref "IC27") (pin "G8") (pinfunction "VCCINT_G8") (pintype "power_in"))
      (node (ref "IC27") (pin "H7") (pinfunction "VCCINT_H7") (pintype "power_in"))
      (node (ref "IC27") (pin "H9") (pinfunction "VCCINT_H9") (pintype "power_in"))
      (node (ref "IC27") (pin "J12") (pinfunction "VCCINT_J12") (pintype "power_in"))
      (node (ref "IC27") (pin "J8") (pinfunction "VCCINT_J8") (pintype "power_in"))
      (node (ref "IC27") (pin "K11") (pinfunction "VCCINT_K11") (pintype "power_in"))
      (node (ref "IC27") (pin "K7") (pinfunction "VCCINT_K7") (pintype "power_in"))
      (node (ref "IC27") (pin "L12") (pinfunction "VCCINT_L12") (pintype "power_in"))
      (node (ref "IC27") (pin "L8") (pinfunction "VCCINT_L8") (pintype "power_in"))
      (node (ref "IC27") (pin "M11") (pinfunction "VCCINT_M11") (pintype "power_in"))
      (node (ref "IC27") (pin "M7") (pinfunction "VCCINT_M7") (pintype "power_in"))
      (node (ref "IC27") (pin "N10") (pinfunction "VCCINT_N10") (pintype "power_in"))
      (node (ref "IC27") (pin "N12") (pinfunction "VCCINT_N12") (pintype "power_in"))
      (node (ref "IC27") (pin "N8") (pinfunction "VCCINT_N8") (pintype "power_in"))
      (node (ref "IC27") (pin "P11") (pinfunction "VCCINT_P11") (pintype "power_in"))
      (node (ref "IC27") (pin "P9") (pinfunction "VCCINT_P9") (pintype "power_in"))
    )
    (net (code "7") (name "P1V8F") (class "Default")
      (node (ref "IC27") (pin "E11") (pinfunction "VCCBATT_0_E11") (pintype "power_in"))
      (node (ref "L36") (pin "1") (pinfunction "1_1") (pintype "passive"))
    )
    (net (code "8") (name "P2V5F") (class "Default")
      (node (ref "C265") (pin "2") (pinfunction "2_2") (pintype "passive"))
      (node (ref "C266") (pin "2") (pinfunction "2_2") (pintype "passive"))
      (node (ref "C267") (pin "2") (pinfunction "2_2") (pintype "passive"))
      (node (ref "C268") (pin "2") (pinfunction "2_2") (pintype "passive"))
      (node (ref "C269") (pin "2") (pinfunction "2_2") (pintype "passive"))
      (node (ref "C270") (pin "2") (pinfunction "2_2") (pintype "passive"))
      (node (ref "C271") (pin "2") (pinfunction "2_2") (pintype "passive"))
      (node (ref "C272") (pin "2") (pinfunction "2_2") (pintype "passive"))
      (node (ref "C273") (pin "2") (pinfunction "2_2") (pintype "passive"))
      (node (ref "C274") (pin "2") (pinfunction "2_2") (pintype "passive"))
      (node (ref "C275") (pin "2") (pinfunction "2_2") (pintype "passive"))
      (node (ref "C276") (pin "2") (pinfunction "2_2") (pintype "passive"))
      (node (ref "C277") (pin "2") (pinfunction "2_2") (pintype "passive"))
      (node (ref "IC27") (pin "A16") (pinfunction "VCCO_15_A16") (pintype "power_in"))
      (node (ref "IC27") (pin "B13") (pinfunction "VCCO_15_B13") (pintype "power_in"))
      (node (ref "IC27") (pin "C10") (pinfunction "VCCO_15_C10") (pintype "power_in"))
      (node (ref "IC27") (pin "D17") (pinfunction "VCCO_15_D17") (pintype "power_in"))
      (node (ref "IC27") (pin "E14") (pinfunction "VCCO_15_E14") (pintype "power_in"))
      (node (ref "IC27") (pin "G18") (pinfunction "VCCO_15_G18") (pintype "power_in"))
      (node (ref "IC27") (pin "H15") (pinfunction "VCCO_15_H15") (pintype "power_in"))
      (node (ref "IC27") (pin "L6") (pinfunction "VCCO_34_L6") (pintype "power_in"))
      (node (ref "IC27") (pin "M3") (pinfunction "VCCO_34_M3") (pintype "power_in"))
      (node (ref "IC27") (pin "P7") (pinfunction "VCCO_34_P7") (pintype "power_in"))
      (node (ref "IC27") (pin "R4") (pinfunction "VCCO_34_R4") (pintype "power_in"))
      (node (ref "IC27") (pin "T1") (pinfunction "VCCO_34_T1") (pintype "power_in"))
      (node (ref "IC27") (pin "V5") (pinfunction "VCCO_34_V5") (pintype "power_in"))
    )
    (net (code "9") (name "P3V3F") (class "Default")
      (node (ref "C278") (pin "2") (pinfunction "2_2") (pintype "passive"))
      (node (ref "C279") (pin "2") (pinfunction "2_2") (pintype "passive"))
      (node (ref "C280") (pin "2") (pinfunction "2_2") (pintype "passive"))
      (node (ref "C281") (pin "2") (pinfunction "2_2") (pintype "passive"))
      (node (ref "C282") (pin "2") (pinfunction "2_2") (pintype "passive"))
      (node (ref "C283") (pin "2") (pinfunction "2_2") (pintype "passive"))
      (node (ref "C284") (pin "2") (pinfunction "2_2") (pintype "passive"))
      (node (ref "C285") (pin "2") (pinfunction "2_2") (pintype "passive"))
      (node (ref "C286") (pin "2") (pinfunction "2_2") (pintype "passive"))
      (node (ref "C287") (pin "2") (pinfunction "2_2") (pintype "passive"))
      (node (ref "IC27") (pin "E10") (pinfunction "VCCO_0_E10") (pintype "power_in"))
      (node (ref "IC27") (pin "L16") (pinfunction "VCCO_14_L16") (pintype "power_in"))
      (node (ref "IC27") (pin "P17") (pinfunction "VCCO_14_P17") (pintype "power_in"))
      (node (ref "IC27") (pin "R10") (pinfunction "VCCO_0_R10") (pintype "power_in"))
      (node (ref "IC27") (pin "R14") (pinfunction "VCCO_14_R14") (pintype "power_in"))
      (node (ref "IC27") (pin "T11") (pinfunction "VCCO_14_T11") (pintype "power_in"))
      (node (ref "IC27") (pin "U18") (pinfunction "VCCO_14_U18") (pintype "power_in"))
      (node (ref "IC27") (pin "U8") (pinfunction "VCCO_14_U8") (pintype "power_in"))
      (node (ref "IC27") (pin "V15") (pinfunction "VCCO_14_V15") (pintype "power_in"))
    )
    (net (code "10") (name "VCCAUX") (class "Default")
      (node (ref "C238") (pin "2") (pinfunction "2_2") (pintype "passive"))
      (node (ref "C239") (pin "2") (pinfunction "2_2") (pintype "passive"))
      (node (ref "C240") (pin "2") (pinfunction "2_2") (pintype "passive"))
      (node (ref "C241") (pin "2") (pinfunction "2_2") (pintype "passive"))
      (node (ref "C242") (pin "2") (pinfunction "2_2") (pintype "passive"))
      (node (ref "IC27") (pin "G12") (pinfunction "VCCAUX_G12") (pintype "power_in"))
      (node (ref "IC27") (pin "H13") (pinfunction "VCCAUX_H13") (pintype "power_in"))
      (node (ref "IC27") (pin "K13") (pinfunction "VCCAUX_K13") (pintype "power_in"))
      (node (ref "IC27") (pin "M13") (pinfunction "VCCAUX_M13") (pintype "power_in"))
      (node (ref "IC27") (pin "P13") (pinfunction "VCCAUX_P13") (pintype "power_in"))
    )
    (net (code "11") (name "VCCBRAM") (class "Default")
      (node (ref "C262") (pin "2") (pinfunction "2_2") (pintype "passive"))
      (node (ref "C263") (pin "2") (pinfunction "2_2") (pintype "passive"))
      (node (ref "C264") (pin "2") (pinfunction "2_2") (pintype "passive"))
      (node (ref "IC27") (pin "F11") (pinfunction "VCCBRAM_F11") (pintype "power_in"))
      (node (ref "IC27") (pin "G10") (pinfunction "VCCBRAM_G10") (pintype "power_in"))
      (node (ref "IC27") (pin "H11") (pinfunction "VCCBRAM_H11") (pintype "power_in"))
    )
    (net (code "12") (name "unconnected-(IC27I-GND-PadN7)") (class "Default")
      (node (ref "IC27") (pin "N7") (pinfunction "GND_N7") (pintype "power_in"))
    )
  )
)
